# ckt_diagram_5v_Ac-Dc.net
KiCad netlist of a schematic drawn in EAGLE
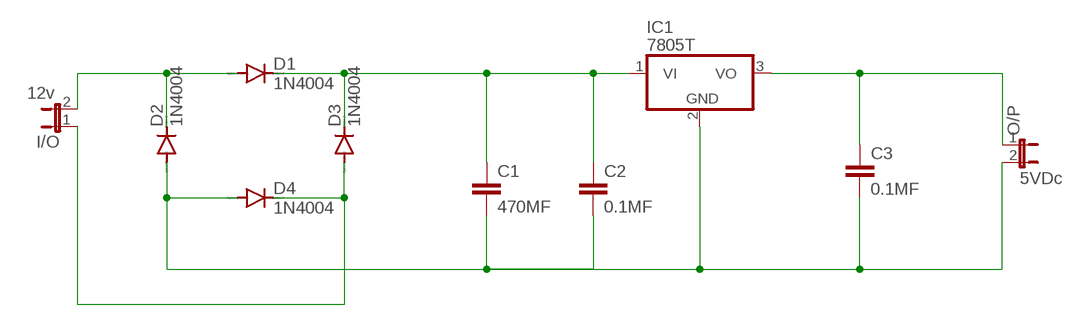
[diagram p0: schematic, sheet 1]

(export (version "E")
  (design (tool "Eeschema 10.0.6"))
  (components
    (comp (ref "C1")
      (value "470MF")
      (footprint "eagle-import:C2.5-2")
      (libsource (lib "eagle-import") (part "C2.5/2"))
    )
    (comp (ref "C2")
      (value "0.1MF")
      (footprint "eagle-import:C2.5-2")
      (libsource (lib "eagle-import") (part "C2.5/2"))
    )
    (comp (ref "C3")
      (value "0.1MF")
      (footprint "eagle-import:C2.5-2")
      (libsource (lib "eagle-import") (part "C2.5/2"))
    )
    (comp (ref "D1")
      (value "1N4004")
      (footprint "eagle-import:DO41-10")
      (libsource (lib "eagle-import") (part "1N4004"))
    )
    (comp (ref "D2")
      (value "1N4004")
      (footprint "eagle-import:DO41-10")
      (libsource (lib "eagle-import") (part "1N4004"))
    )
    (comp (ref "D3")
      (value "1N4004")
      (footprint "eagle-import:DO41-10")
      (libsource (lib "eagle-import") (part "1N4004"))
    )
    (comp (ref "D4")
      (value "1N4004")
      (footprint "eagle-import:DO41-10")
      (libsource (lib "eagle-import") (part "1N4004"))
    )
    (comp (ref "I/O")
      (value "12v")
      (footprint "eagle-import:JP1")
      (libsource (lib "eagle-import") (part "JP1E"))
    )
    (comp (ref "IC1")
      (value "7805T")
      (footprint "eagle-import:TO220H")
      (libsource (lib "eagle-import") (part "78T05"))
    )
    (comp (ref "O/P")
      (value "5VDc")
      (footprint "eagle-import:JP1")
      (libsource (lib "eagle-import") (part "JP1E"))
    )
  )
  (nets
    (net (code "1") (name "Net-(D1-PadA)") (class "Default")
      (node (ref "D1") (pin "A") (pinfunction "A_A") (pintype "passive"))
      (node (ref "D2") (pin "C") (pinfunction "C_C") (pintype "passive"))
      (node (ref "I/O") (pin "2") (pinfunction "2_2") (pintype "passive"))
    )
    (net (code "2") (name "Net-(D3-PadA)") (class "Default")
      (node (ref "D3") (pin "A") (pinfunction "A_A") (pintype "passive"))
      (node (ref "D4") (pin "C") (pinfunction "C_C") (pintype "passive"))
      (node (ref "I/O") (pin "1") (pinfunction "1_1") (pintype "passive"))
    )
    (net (code "3") (name "Net-(IC1-GND)") (class "Default")
      (node (ref "C1") (pin "2") (pinfunction "2_2") (pintype "passive"))
      (node (ref "C2") (pin "2") (pinfunction "2_2") (pintype "passive"))
      (node (ref "C3") (pin "2") (pinfunction "2_2") (pintype "passive"))
      (node (ref "D2") (pin "A") (pinfunction "A_A") (pintype "passive"))
      (node (ref "D4") (pin "A") (pinfunction "A_A") (pintype "passive"))
      (node (ref "IC1") (pin "2") (pinfunction "GND_2") (pintype "passive"))
      (node (ref "O/P") (pin "2") (pinfunction "2_2") (pintype "passive"))
    )
    (net (code "4") (name "Net-(IC1-VI)") (class "Default")
      (node (ref "C1") (pin "1") (pinfunction "1_1") (pintype "passive"))
      (node (ref "C2") (pin "1") (pinfunction "1_1") (pintype "passive"))
      (node (ref "D1") (pin "C") (pinfunction "C_C") (pintype "passive"))
      (node (ref "D3") (pin "C") (pinfunction "C_C") (pintype "passive"))
      (node (ref "IC1") (pin "1") (pinfunction "VI_1") (pintype "input"))
    )
    (net (code "5") (name "Net-(IC1-VO)") (class "Default")
      (node (ref "C3") (pin "1") (pinfunction "1_1") (pintype "passive"))
      (node (ref "IC1") (pin "3") (pinfunction "VO_3") (pintype "passive"))
      (node (ref "O/P") (pin "1") (pinfunction "1_1") (pintype "passive"))
    )
  )
)
